# HF_AMP_DRIVER.net
KiCad netlist of a schematic drawn in Altium Designer
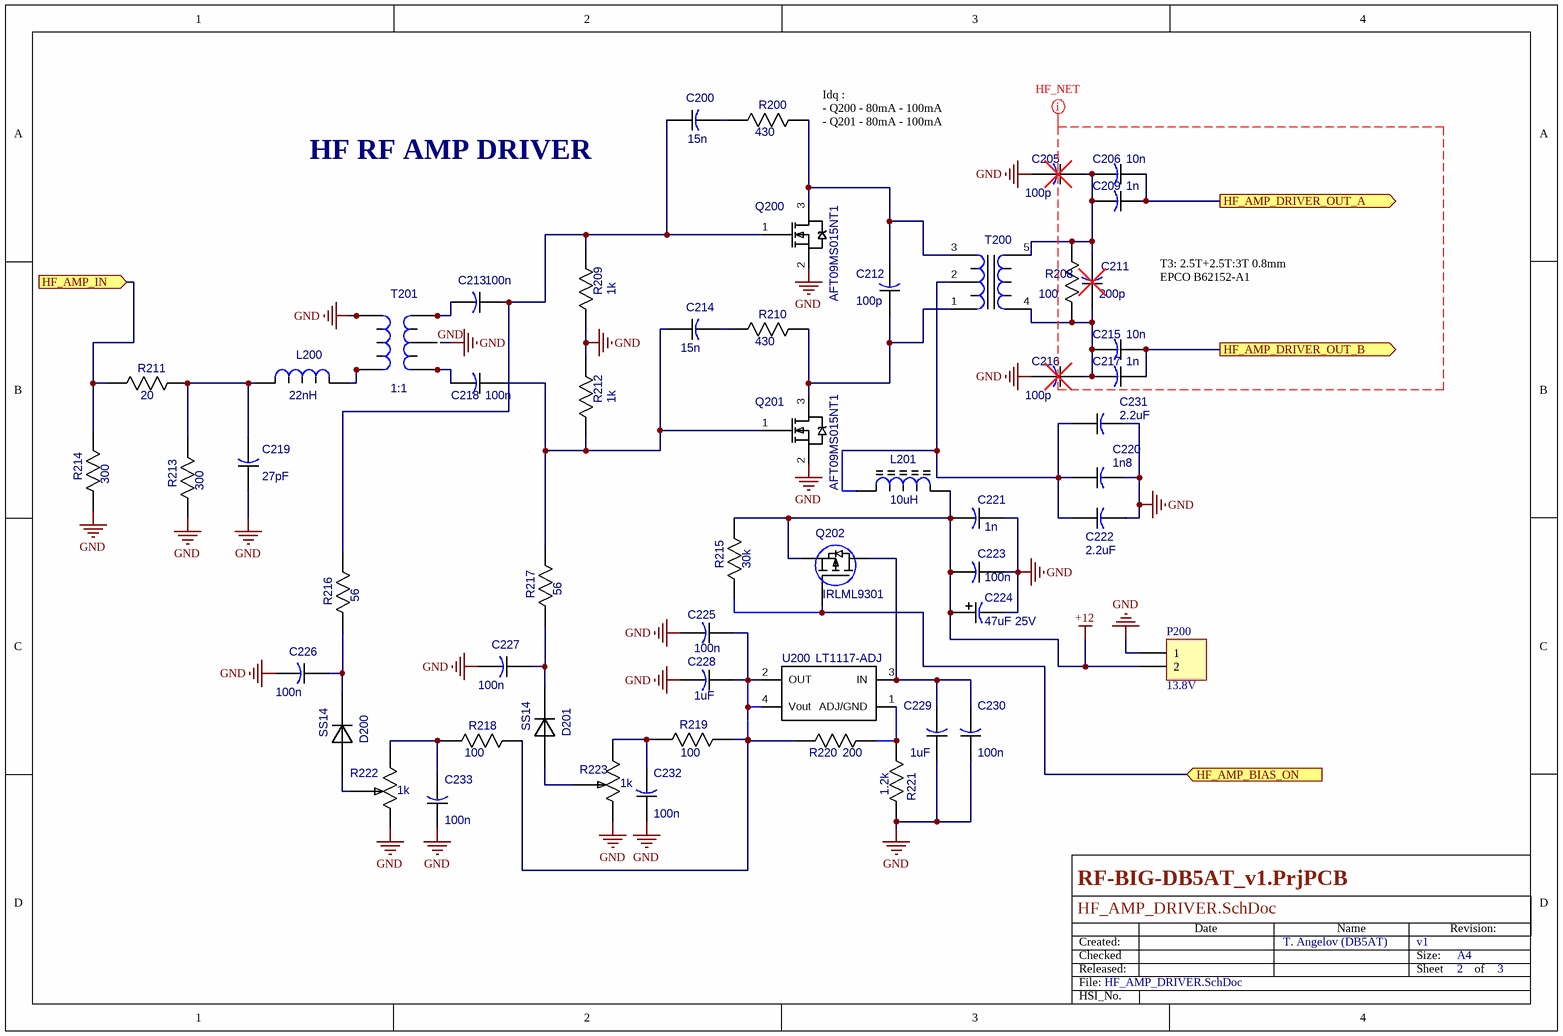
[diagram p0: HF_AMP_DRIVER.SchDoc]

(export (version "E")
  (design (tool "Eeschema 10.0.6"))
  (components
    (comp (ref "C200")
      (value "15n")
      (footprint "CAP_0805")
      (description "CAP_1206")
      (libsource (lib "*") (part "CAP_1206"))
    )
    (comp (ref "C205")
      (value "100p")
      (footprint "CAP_1206")
      (description "CAP_1206")
      (libsource (lib "*") (part "CAP_1206"))
    )
    (comp (ref "C206")
      (value "10n")
      (footprint "CAP_1206")
      (description "CAP_1206")
      (libsource (lib "*") (part "CAP_1206"))
    )
    (comp (ref "C209")
      (value "1n")
      (footprint "CAP_1206")
      (description "CAP_1206")
      (libsource (lib "*") (part "CAP_1206"))
    )
    (comp (ref "C211")
      (value "200p")
      (footprint "CAP_1206")
      (description "CAP_1206")
      (libsource (lib "*") (part "CAP_1206"))
    )
    (comp (ref "C212")
      (value "100p")
      (footprint "CAP_1206")
      (description "CAP_1206")
      (libsource (lib "*") (part "CAP_1206"))
    )
    (comp (ref "C213")
      (value "100n")
      (footprint "CAP_0805")
      (description "CAP_0805")
      (libsource (lib "*") (part "CAP_0805"))
    )
    (comp (ref "C214")
      (value "15n")
      (footprint "CAP_0805")
      (description "CAP_1206")
      (libsource (lib "*") (part "CAP_1206"))
    )
    (comp (ref "C215")
      (value "10n")
      (footprint "CAP_1206")
      (description "CAP_1206")
      (libsource (lib "*") (part "CAP_1206"))
    )
    (comp (ref "C216")
      (value "100p")
      (footprint "CAP_1206")
      (description "CAP_1206")
      (libsource (lib "*") (part "CAP_1206"))
    )
    (comp (ref "C217")
      (value "1n")
      (footprint "CAP_1206")
      (description "CAP_1206")
      (libsource (lib "*") (part "CAP_1206"))
    )
    (comp (ref "C218")
      (value "100n")
      (footprint "CAP_0805")
      (description "CAP_0805")
      (libsource (lib "*") (part "CAP_0805"))
    )
    (comp (ref "C219")
      (value "27pF")
      (footprint "CAP_0805")
      (description "CAP_0805")
      (libsource (lib "*") (part "CAP_0805"))
    )
    (comp (ref "C220")
      (value "1n8")
      (footprint "CAP_1206")
      (description "CAP_1206")
      (libsource (lib "*") (part "CAP_1206"))
    )
    (comp (ref "C221")
      (value "1n")
      (footprint "CAP_0805")
      (description "CAP_0805")
      (libsource (lib "*") (part "CAP_0805"))
    )
    (comp (ref "C222")
      (value "2.2uF")
      (footprint "CAP_1206")
      (description "CAP_1206")
      (libsource (lib "*") (part "CAP_1206"))
    )
    (comp (ref "C223")
      (value "100n")
      (footprint "CAP_0805")
      (description "CAP_0805")
      (libsource (lib "*") (part "CAP_0805"))
    )
    (comp (ref "C224")
      (value "47uF 25V")
      (footprint "CAPAE_6.6x6.6h5.4")
      (description "CAPAE_6.6x6.6h5.4")
      (libsource (lib "*") (part "CAPAE_6.6x6.6h5.4"))
    )
    (comp (ref "C225")
      (value "100n")
      (footprint "CAP_0805")
      (description "CAP_0805")
      (libsource (lib "*") (part "CAP_0805"))
    )
    (comp (ref "C226")
      (value "100n")
      (footprint "CAP_0805")
      (description "CAP_0805")
      (libsource (lib "*") (part "CAP_0805"))
    )
    (comp (ref "C227")
      (value "100n")
      (footprint "CAP_0805")
      (description "CAP_0805")
      (libsource (lib "*") (part "CAP_0805"))
    )
    (comp (ref "C228")
      (value "1uF")
      (footprint "CAP_0805")
      (description "CAP_0805")
      (libsource (lib "*") (part "CAP_0805"))
    )
    (comp (ref "C229")
      (value "1uF")
      (footprint "CAP_0805")
      (description "CAP_0805")
      (libsource (lib "*") (part "CAP_0805"))
    )
    (comp (ref "C230")
      (value "100n")
      (footprint "CAP_0805")
      (description "CAP_0805")
      (libsource (lib "*") (part "CAP_0805"))
    )
    (comp (ref "C231")
      (value "2.2uF")
      (footprint "CAP_1206")
      (description "CAP_1206")
      (libsource (lib "*") (part "CAP_1206"))
    )
    (comp (ref "C232")
      (value "100n")
      (footprint "CAP_0805")
      (description "CAP_0805")
      (libsource (lib "*") (part "CAP_0805"))
    )
    (comp (ref "C233")
      (value "100n")
      (footprint "CAP_0805")
      (description "CAP_0805")
      (libsource (lib "*") (part "CAP_0805"))
    )
    (comp (ref "D200") (value "SS14") (footprint "SS14") (libsource (lib "*") (part "SS14")))
    (comp (ref "D201") (value "SS14") (footprint "SS14") (libsource (lib "*") (part "SS14")))
    (comp (ref "L200")
      (value "22nH")
      (footprint "IND_0805")
      (description "IND_0805")
      (libsource (lib "*") (part "IND_0805"))
    )
    (comp (ref "L201")
      (value "10uH")
      (footprint "IND_FERRITE_CORE")
      (description "Inductor")
      (libsource (lib "*") (part "IND_FERRITE_CORE"))
    )
    (comp (ref "P200")
      (value "13.8V")
      (footprint "2 Pole Screw")
      (description "Header, 2-Pin")
      (fields (field (name "PUBLISHER") "Altium Limited"))
      (libsource (lib "Miscellaneous Connectors") (part "Header 2"))
    )
    (comp (ref "Q200")
      (value "AFT09MS015NT1")
      (footprint "AFT09MS015NT1")
      (libsource (lib "RF-UNIT-QRP") (part "AFT09MS015NT1"))
    )
    (comp (ref "Q201")
      (value "AFT09MS015NT1")
      (footprint "AFT09MS015NT1")
      (libsource (lib "RF-UNIT-QRP") (part "AFT09MS015NT1"))
    )
    (comp (ref "Q202")
      (value "IRLML9301")
      (footprint "SOT23")
      (description "MOSFET")
      (libsource (lib "*") (part "MOSFET_ENH_PD"))
    )
    (comp (ref "R200")
      (value "430")
      (footprint "RES_0805")
      (description "RES_1206")
      (libsource (lib "*") (part "RES_1206"))
    )
    (comp (ref "R208")
      (value "100")
      (footprint "RES_1206")
      (description "RES_1206")
      (libsource (lib "*") (part "RES_1206"))
    )
    (comp (ref "R209")
      (value "1k")
      (footprint "RES_0805")
      (description "RES_0805")
      (libsource (lib "*") (part "RES_0805"))
    )
    (comp (ref "R210")
      (value "430")
      (footprint "RES_0805")
      (description "RES_1206")
      (libsource (lib "*") (part "RES_1206"))
    )
    (comp (ref "R211")
      (value "20")
      (footprint "RES_1206")
      (description "RES_1206")
      (libsource (lib "*") (part "RES_1206"))
    )
    (comp (ref "R212")
      (value "1k")
      (footprint "RES_0805")
      (description "RES_0805")
      (libsource (lib "*") (part "RES_0805"))
    )
    (comp (ref "R213")
      (value "300")
      (footprint "RES_1206")
      (description "RES_1206")
      (libsource (lib "*") (part "RES_1206"))
    )
    (comp (ref "R214")
      (value "300")
      (footprint "RES_1206")
      (description "RES_1206")
      (libsource (lib "*") (part "RES_1206"))
    )
    (comp (ref "R215")
      (value "30k")
      (footprint "RES_0805")
      (description "RES_0805")
      (libsource (lib "*") (part "RES_0805"))
    )
    (comp (ref "R216")
      (value "56")
      (footprint "RES_0805")
      (description "RES_0805")
      (libsource (lib "*") (part "RES_0805"))
    )
    (comp (ref "R217")
      (value "56")
      (footprint "RES_0805")
      (description "RES_0805")
      (libsource (lib "*") (part "RES_0805"))
    )
    (comp (ref "R218")
      (value "100")
      (footprint "RES_0805")
      (description "RES_0805")
      (libsource (lib "*") (part "RES_0805"))
    )
    (comp (ref "R219")
      (value "100")
      (footprint "RES_0805")
      (description "RES_0805")
      (libsource (lib "*") (part "RES_0805"))
    )
    (comp (ref "R220")
      (value "200")
      (footprint "RES_0805")
      (description "RES_0805")
      (libsource (lib "*") (part "RES_0805"))
    )
    (comp (ref "R221")
      (value "1.2k")
      (footprint "RES_0805")
      (description "RES_0805")
      (libsource (lib "*") (part "RES_0805"))
    )
    (comp (ref "R222")
      (value "1k")
      (footprint "306J")
      (description "306J")
      (fields (field (name "Comment") "ADJ-1k"))
      (libsource (lib "*") (part "306J"))
    )
    (comp (ref "R223")
      (value "1k")
      (footprint "306J")
      (description "306J")
      (fields (field (name "Comment") "ADJ-1k"))
      (libsource (lib "*") (part "306J"))
    )
    (comp (ref "T200")
      (value "TRANSF_HF3")
      (footprint "TRANSF_HF3")
      (libsource (lib "RF-UNIT-BIG") (part "TRANSF_RF3"))
    )
    (comp (ref "T201")
      (value "1:1")
      (footprint "TRANSF_ACORE2")
      (libsource (lib "RF-UNIT_1") (part "TRANSF_ACORE2"))
    )
    (comp (ref "U200")
      (value "LT1117-ADJ")
      (footprint "LT1117IST-ADJ")
      (description "LT1117IST-ADJ")
      (libsource (lib "*") (part "LT1117IST-ADJ"))
    )
  )
  (nets
    (net (code "1") (name "+12") (class "Default")
      (node (ref "C221") (pin "2") (pinfunction "2_2") (pintype "passive"))
      (node (ref "C223") (pin "2") (pinfunction "2_2") (pintype "passive"))
      (node (ref "C224") (pin "1") (pinfunction "PLUS_1") (pintype "passive"))
      (node (ref "L201") (pin "2") (pinfunction "B_2") (pintype "passive"))
      (node (ref "P200") (pin "2") (pinfunction "2_2") (pintype "passive"))
      (node (ref "Q202") (pin "2") (pinfunction "S_2") (pintype "passive"))
      (node (ref "R215") (pin "2") (pinfunction "2_2") (pintype "passive"))
    )
    (net (code "2") (name "/HF_AMP_BIAS_ON") (class "Default")
      (node (ref "Q202") (pin "1") (pinfunction "G_1") (pintype "passive"))
      (node (ref "R215") (pin "1") (pinfunction "1_1") (pintype "passive"))
    )
    (net (code "3") (name "/HF_AMP_DRIVER_OUT_A") (class "Default")
      (node (ref "C206") (pin "1") (pinfunction "1_1") (pintype "passive"))
      (node (ref "C209") (pin "1") (pinfunction "1_1") (pintype "passive"))
    )
    (net (code "4") (name "/HF_AMP_DRIVER_OUT_B") (class "Default")
      (node (ref "C215") (pin "1") (pinfunction "1_1") (pintype "passive"))
      (node (ref "C217") (pin "1") (pinfunction "1_1") (pintype "passive"))
    )
    (net (code "5") (name "/HF_AMP_IN") (class "Default")
      (node (ref "R211") (pin "1") (pinfunction "1_1") (pintype "passive"))
      (node (ref "R214") (pin "2") (pinfunction "2_2") (pintype "passive"))
    )
    (net (code "6") (name "GND") (class "Default")
      (node (ref "C205") (pin "2") (pinfunction "2_2") (pintype "passive"))
      (node (ref "C216") (pin "2") (pinfunction "2_2") (pintype "passive"))
      (node (ref "C219") (pin "1") (pinfunction "1_1") (pintype "passive"))
      (node (ref "C220") (pin "2") (pinfunction "2_2") (pintype "passive"))
      (node (ref "C221") (pin "1") (pinfunction "1_1") (pintype "passive"))
      (node (ref "C222") (pin "2") (pinfunction "2_2") (pintype "passive"))
      (node (ref "C223") (pin "1") (pinfunction "1_1") (pintype "passive"))
      (node (ref "C224") (pin "2") (pinfunction "MINUS_2") (pintype "passive"))
      (node (ref "C225") (pin "2") (pinfunction "2_2") (pintype "passive"))
      (node (ref "C226") (pin "2") (pinfunction "2_2") (pintype "passive"))
      (node (ref "C227") (pin "2") (pinfunction "2_2") (pintype "passive"))
      (node (ref "C228") (pin "2") (pinfunction "2_2") (pintype "passive"))
      (node (ref "C229") (pin "1") (pinfunction "1_1") (pintype "passive"))
      (node (ref "C230") (pin "1") (pinfunction "1_1") (pintype "passive"))
      (node (ref "C231") (pin "2") (pinfunction "2_2") (pintype "passive"))
      (node (ref "C232") (pin "1") (pinfunction "1_1") (pintype "passive"))
      (node (ref "C233") (pin "1") (pinfunction "1_1") (pintype "passive"))
      (node (ref "P200") (pin "1") (pinfunction "1_1") (pintype "passive"))
      (node (ref "Q200") (pin "2") (pinfunction "S_2") (pintype "passive"))
      (node (ref "Q201") (pin "2") (pinfunction "S_2") (pintype "passive"))
      (node (ref "R209") (pin "1") (pinfunction "1_1") (pintype "passive"))
      (node (ref "R212") (pin "2") (pinfunction "2_2") (pintype "passive"))
      (node (ref "R213") (pin "1") (pinfunction "1_1") (pintype "passive"))
      (node (ref "R214") (pin "1") (pinfunction "1_1") (pintype "passive"))
      (node (ref "R221") (pin "2") (pinfunction "2_2") (pintype "passive"))
      (node (ref "R222") (pin "1") (pinfunction "CCW_1") (pintype "passive"))
      (node (ref "R223") (pin "1") (pinfunction "CCW_1") (pintype "passive"))
      (node (ref "T201") (pin "11") (pinfunction "0_11") (pintype "passive"))
      (node (ref "T201") (pin "2") (pinfunction "S2_2") (pintype "passive"))
      (node (ref "T201") (pin "4") (pinfunction "P2_4") (pintype "passive"))
      (node (ref "T201") (pin "8") (pinfunction "S2_8") (pintype "passive"))
    )
    (net (code "7") (name "Net-(C200-Pad2)") (class "Default")
      (node (ref "C200") (pin "2") (pinfunction "2_2") (pintype "passive"))
      (node (ref "R200") (pin "1") (pinfunction "1_1") (pintype "passive"))
    )
    (net (code "8") (name "Net-(C214-Pad2)") (class "Default")
      (node (ref "C214") (pin "2") (pinfunction "2_2") (pintype "passive"))
      (node (ref "R210") (pin "1") (pinfunction "1_1") (pintype "passive"))
    )
    (net (code "9") (name "Net-(C219-Pad2)") (class "Default")
      (node (ref "C219") (pin "2") (pinfunction "2_2") (pintype "passive"))
      (node (ref "L200") (pin "1") (pinfunction "1_1") (pintype "passive"))
      (node (ref "R211") (pin "2") (pinfunction "2_2") (pintype "passive"))
      (node (ref "R213") (pin "2") (pinfunction "2_2") (pintype "passive"))
    )
    (net (code "10") (name "Net-(D200-A)") (class "Default")
      (node (ref "D200") (pin "2") (pinfunction "A_2") (pintype "passive"))
      (node (ref "R222") (pin "2") (pinfunction "W_2") (pintype "passive"))
    )
    (net (code "11") (name "Net-(D200-K)") (class "Default")
      (node (ref "C226") (pin "1") (pinfunction "1_1") (pintype "passive"))
      (node (ref "D200") (pin "1") (pinfunction "K_1") (pintype "passive"))
      (node (ref "R216") (pin "1") (pinfunction "1_1") (pintype "passive"))
    )
    (net (code "12") (name "Net-(D201-A)") (class "Default")
      (node (ref "D201") (pin "2") (pinfunction "A_2") (pintype "passive"))
      (node (ref "R223") (pin "2") (pinfunction "W_2") (pintype "passive"))
    )
    (net (code "13") (name "Net-(D201-K)") (class "Default")
      (node (ref "C227") (pin "1") (pinfunction "1_1") (pintype "passive"))
      (node (ref "D201") (pin "1") (pinfunction "K_1") (pintype "passive"))
      (node (ref "R217") (pin "1") (pinfunction "1_1") (pintype "passive"))
    )
    (net (code "14") (name "Net-(L201-A)") (class "Default")
      (node (ref "C220") (pin "1") (pinfunction "1_1") (pintype "passive"))
      (node (ref "C222") (pin "1") (pinfunction "1_1") (pintype "passive"))
      (node (ref "C231") (pin "1") (pinfunction "1_1") (pintype "passive"))
      (node (ref "L201") (pin "1") (pinfunction "A_1") (pintype "passive"))
      (node (ref "T200") (pin "2") (pinfunction "S3_2") (pintype "passive"))
    )
    (net (code "15") (name "Net-(Q200-D)") (class "Default")
      (node (ref "C212") (pin "2") (pinfunction "2_2") (pintype "passive"))
      (node (ref "Q200") (pin "3") (pinfunction "D_3") (pintype "passive"))
      (node (ref "R200") (pin "2") (pinfunction "2_2") (pintype "passive"))
      (node (ref "T200") (pin "3") (pinfunction "S1_3") (pintype "passive"))
    )
    (net (code "16") (name "Net-(Q200-G)") (class "Default")
      (node (ref "C200") (pin "1") (pinfunction "1_1") (pintype "passive"))
      (node (ref "C213") (pin "1") (pinfunction "1_1") (pintype "passive"))
      (node (ref "Q200") (pin "1") (pinfunction "G_1") (pintype "passive"))
      (node (ref "R209") (pin "2") (pinfunction "2_2") (pintype "passive"))
      (node (ref "R216") (pin "2") (pinfunction "2_2") (pintype "passive"))
    )
    (net (code "17") (name "Net-(Q201-D)") (class "Default")
      (node (ref "C212") (pin "1") (pinfunction "1_1") (pintype "passive"))
      (node (ref "Q201") (pin "3") (pinfunction "D_3") (pintype "passive"))
      (node (ref "R210") (pin "2") (pinfunction "2_2") (pintype "passive"))
      (node (ref "T200") (pin "1") (pinfunction "S2_1") (pintype "passive"))
    )
    (net (code "18") (name "Net-(Q201-G)") (class "Default")
      (node (ref "C214") (pin "1") (pinfunction "1_1") (pintype "passive"))
      (node (ref "C218") (pin "1") (pinfunction "1_1") (pintype "passive"))
      (node (ref "Q201") (pin "1") (pinfunction "G_1") (pintype "passive"))
      (node (ref "R212") (pin "1") (pinfunction "1_1") (pintype "passive"))
      (node (ref "R217") (pin "2") (pinfunction "2_2") (pintype "passive"))
    )
    (net (code "19") (name "Net-(Q202-D)") (class "Default")
      (node (ref "C229") (pin "2") (pinfunction "2_2") (pintype "passive"))
      (node (ref "C230") (pin "2") (pinfunction "2_2") (pintype "passive"))
      (node (ref "Q202") (pin "3") (pinfunction "D_3") (pintype "passive"))
      (node (ref "U200") (pin "3") (pinfunction "IN_3") (pintype "passive"))
    )
    (net (code "20") (name "Net-(R222-CW)") (class "Default")
      (node (ref "C233") (pin "2") (pinfunction "2_2") (pintype "passive"))
      (node (ref "R218") (pin "1") (pinfunction "1_1") (pintype "passive"))
      (node (ref "R222") (pin "3") (pinfunction "CW_3") (pintype "passive"))
    )
    (net (code "21") (name "Net-(R223-CW)") (class "Default")
      (node (ref "C232") (pin "2") (pinfunction "2_2") (pintype "passive"))
      (node (ref "R219") (pin "1") (pinfunction "1_1") (pintype "passive"))
      (node (ref "R223") (pin "3") (pinfunction "CW_3") (pintype "passive"))
    )
    (net (code "22") (name "Net-(T200-P1)") (class "Default")
      (node (ref "C205") (pin "1") (pinfunction "1_1") (pintype "passive"))
      (node (ref "C206") (pin "2") (pinfunction "2_2") (pintype "passive"))
      (node (ref "C209") (pin "2") (pinfunction "2_2") (pintype "passive"))
      (node (ref "C211") (pin "2") (pinfunction "2_2") (pintype "passive"))
      (node (ref "R208") (pin "2") (pinfunction "2_2") (pintype "passive"))
      (node (ref "T200") (pin "5") (pinfunction "P1_5") (pintype "passive"))
    )
    (net (code "23") (name "Net-(T200-P2)") (class "Default")
      (node (ref "C211") (pin "1") (pinfunction "1_1") (pintype "passive"))
      (node (ref "C215") (pin "2") (pinfunction "2_2") (pintype "passive"))
      (node (ref "C216") (pin "1") (pinfunction "1_1") (pintype "passive"))
      (node (ref "C217") (pin "2") (pinfunction "2_2") (pintype "passive"))
      (node (ref "R208") (pin "1") (pinfunction "1_1") (pintype "passive"))
      (node (ref "T200") (pin "4") (pinfunction "P2_4") (pintype "passive"))
    )
    (net (code "24") (name "Net-(T201-P1)") (class "Default")
      (node (ref "L200") (pin "2") (pinfunction "2_2") (pintype "passive"))
      (node (ref "T201") (pin "10") (pinfunction "0_10") (pintype "passive"))
      (node (ref "T201") (pin "6") (pinfunction "P1_6") (pintype "passive"))
    )
    (net (code "25") (name "Net-(T201-S1)") (class "Default")
      (node (ref "C218") (pin "2") (pinfunction "2_2") (pintype "passive"))
      (node (ref "T201") (pin "1") (pinfunction "S1_1") (pintype "passive"))
      (node (ref "T201") (pin "7") (pinfunction "0_7") (pintype "passive"))
    )
    (net (code "26") (name "Net-(T201-S3)") (class "Default")
      (node (ref "C213") (pin "2") (pinfunction "2_2") (pintype "passive"))
      (node (ref "T201") (pin "3") (pinfunction "S3_3") (pintype "passive"))
      (node (ref "T201") (pin "9") (pinfunction "0_9") (pintype "passive"))
    )
    (net (code "27") (name "Net-(U200-ADJ{slash}GND)") (class "Default")
      (node (ref "R220") (pin "2") (pinfunction "2_2") (pintype "passive"))
      (node (ref "R221") (pin "1") (pinfunction "1_1") (pintype "passive"))
      (node (ref "U200") (pin "1") (pinfunction "ADJ/GND_1") (pintype "passive"))
    )
    (net (code "28") (name "Net-(U200-OUT)") (class "Default")
      (node (ref "C225") (pin "1") (pinfunction "1_1") (pintype "passive"))
      (node (ref "C228") (pin "1") (pinfunction "1_1") (pintype "passive"))
      (node (ref "R218") (pin "2") (pinfunction "2_2") (pintype "passive"))
      (node (ref "R219") (pin "2") (pinfunction "2_2") (pintype "passive"))
      (node (ref "R220") (pin "1") (pinfunction "1_1") (pintype "passive"))
      (node (ref "U200") (pin "2") (pinfunction "OUT_2") (pintype "passive"))
      (node (ref "U200") (pin "4") (pinfunction "Vout_4") (pintype "passive"))
    )
  )
)
